# 2013_fdp_banc_de_test.net
KiCad netlist of a schematic drawn in Altium Designer
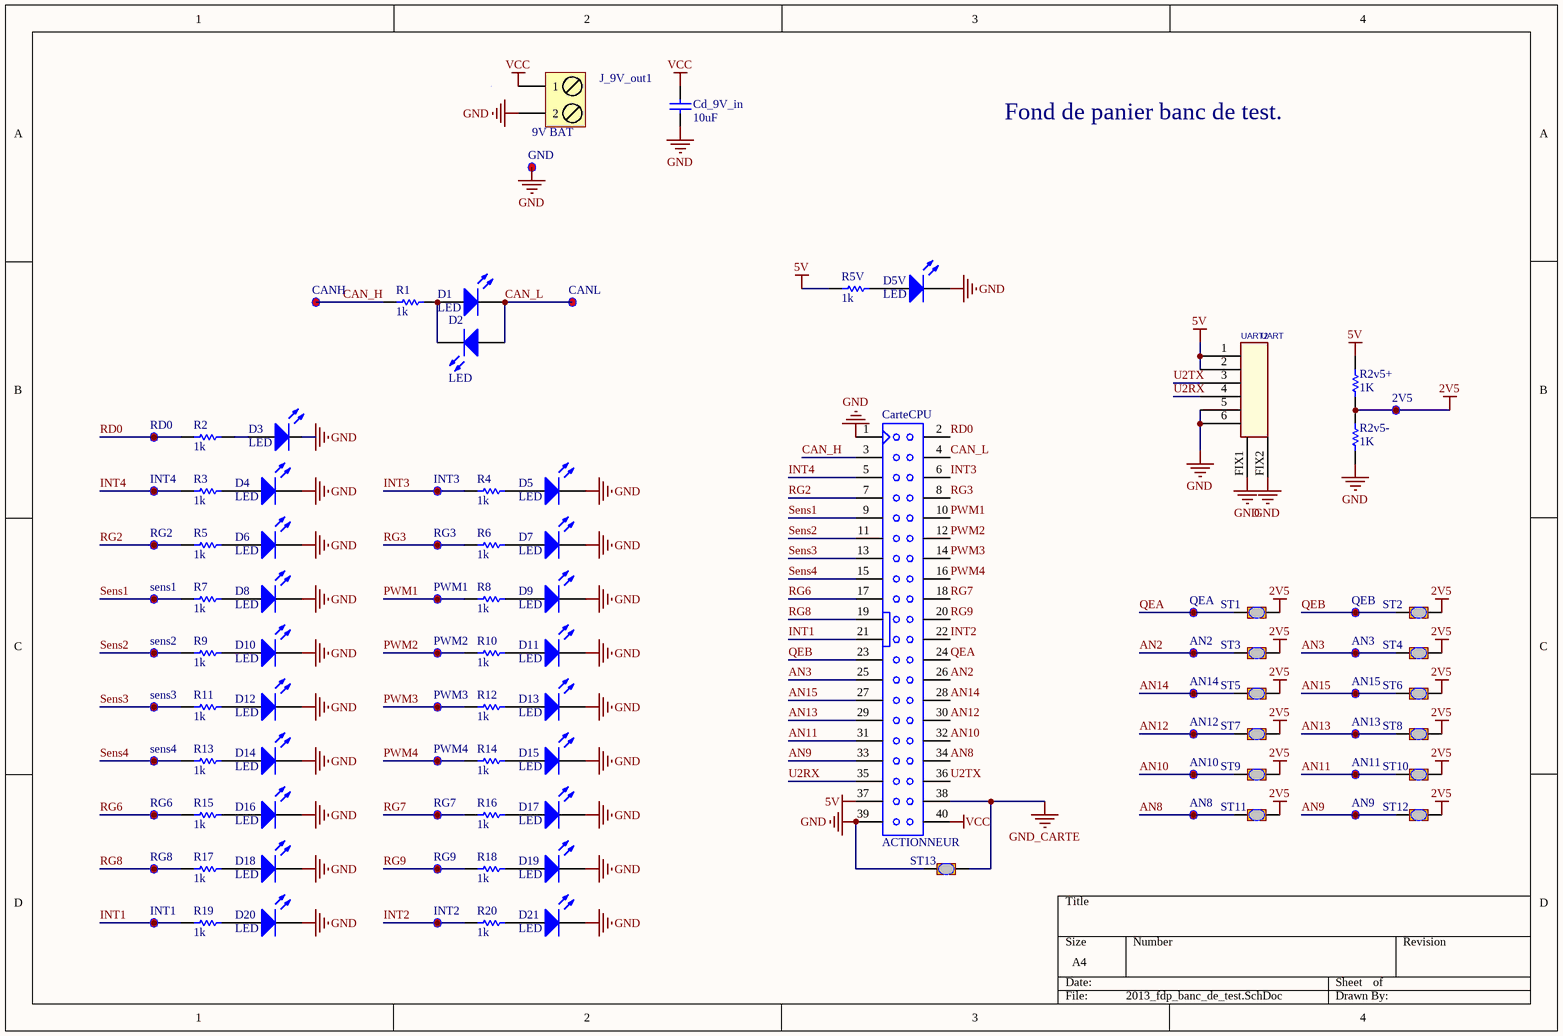
[diagram p0: 2013_fdp_banc_de_test.SchDoc]

(export (version "E")
  (design (tool "Eeschema 10.0.6"))
  (components
    (comp (ref "2V5")
      (value "Name")
      (footprint "Point Test_D0.9_P0.5mm")
      (description "Point test")
      (fields (field (name "PUBLISHER") "Damien GUITTON"))
      (libsource (lib "DG_Connecteur") (part "Point Test_2"))
    )
    (comp (ref "AN2")
      (value "Name")
      (footprint "Point Test_D0.9_P0.5mm")
      (description "Point test")
      (fields (field (name "PUBLISHER") "Damien GUITTON"))
      (libsource (lib "DG_Connecteur") (part "Point Test_2"))
    )
    (comp (ref "AN3")
      (value "Name")
      (footprint "Point Test_D0.9_P0.5mm")
      (description "Point test")
      (fields (field (name "PUBLISHER") "Damien GUITTON"))
      (libsource (lib "DG_Connecteur") (part "Point Test_2"))
    )
    (comp (ref "AN8")
      (value "Name")
      (footprint "Point Test_D0.9_P0.5mm")
      (description "Point test")
      (fields (field (name "PUBLISHER") "Damien GUITTON"))
      (libsource (lib "DG_Connecteur") (part "Point Test_2"))
    )
    (comp (ref "AN9")
      (value "Name")
      (footprint "Point Test_D0.9_P0.5mm")
      (description "Point test")
      (fields (field (name "PUBLISHER") "Damien GUITTON"))
      (libsource (lib "DG_Connecteur") (part "Point Test_2"))
    )
    (comp (ref "AN10")
      (value "Name")
      (footprint "Point Test_D0.9_P0.5mm")
      (description "Point test")
      (fields (field (name "PUBLISHER") "Damien GUITTON"))
      (libsource (lib "DG_Connecteur") (part "Point Test_2"))
    )
    (comp (ref "AN11")
      (value "Name")
      (footprint "Point Test_D0.9_P0.5mm")
      (description "Point test")
      (fields (field (name "PUBLISHER") "Damien GUITTON"))
      (libsource (lib "DG_Connecteur") (part "Point Test_2"))
    )
    (comp (ref "AN12")
      (value "Name")
      (footprint "Point Test_D0.9_P0.5mm")
      (description "Point test")
      (fields (field (name "PUBLISHER") "Damien GUITTON"))
      (libsource (lib "DG_Connecteur") (part "Point Test_2"))
    )
    (comp (ref "AN13")
      (value "Name")
      (footprint "Point Test_D0.9_P0.5mm")
      (description "Point test")
      (fields (field (name "PUBLISHER") "Damien GUITTON"))
      (libsource (lib "DG_Connecteur") (part "Point Test_2"))
    )
    (comp (ref "AN14")
      (value "Name")
      (footprint "Point Test_D0.9_P0.5mm")
      (description "Point test")
      (fields (field (name "PUBLISHER") "Damien GUITTON"))
      (libsource (lib "DG_Connecteur") (part "Point Test_2"))
    )
    (comp (ref "AN15")
      (value "Name")
      (footprint "Point Test_D0.9_P0.5mm")
      (description "Point test")
      (fields (field (name "PUBLISHER") "Damien GUITTON"))
      (libsource (lib "DG_Connecteur") (part "Point Test_2"))
    )
    (comp (ref "CANH")
      (value "Name")
      (footprint "Point Test_D0.9_P0.5mm")
      (description "Point test")
      (fields (field (name "PUBLISHER") "Damien GUITTON"))
      (libsource (lib "DG_Connecteur") (part "Point Test_2"))
    )
    (comp (ref "CANL")
      (value "Name")
      (footprint "Point Test_D0.9_P0.5mm")
      (description "Point test")
      (fields (field (name "PUBLISHER") "Damien GUITTON"))
      (libsource (lib "DG_Connecteur") (part "Point Test_2"))
    )
    (comp (ref "CarteCPU")
      (value "ACTIONNEUR")
      (footprint "HE10/40_MAL_DROIT-FDP-ROBOT")
      (description "Connector; HE10; 40 Position; Male")
      (libsource (lib "miniprojet") (part "HE10/40"))
    )
    (comp (ref "Cd_9V_in")
      (value "10uF")
      (footprint "C0805_N")
      (description "Capacitor")
      (fields (field (name "PUBLISHER") "Altium Limited"))
      (libsource (lib "_ROBOT") (part "Condensateur"))
    )
    (comp (ref "D1")
      (value "LED")
      (footprint "LED_0805")
      (description "Typical LED")
      (fields (field (name "PUBLISHER") "Altium Limited"))
      (libsource (lib "_ROBOT") (part "LED"))
    )
    (comp (ref "D2")
      (value "LED")
      (footprint "LED_0805")
      (description "Typical LED")
      (fields (field (name "PUBLISHER") "Altium Limited"))
      (libsource (lib "_ROBOT") (part "LED"))
    )
    (comp (ref "D3")
      (value "LED")
      (footprint "LED_0805")
      (description "Typical LED")
      (fields (field (name "PUBLISHER") "Altium Limited"))
      (libsource (lib "_ROBOT") (part "LED"))
    )
    (comp (ref "D4")
      (value "LED")
      (footprint "LED_0805")
      (description "Typical LED")
      (fields (field (name "PUBLISHER") "Altium Limited"))
      (libsource (lib "_ROBOT") (part "LED"))
    )
    (comp (ref "D5")
      (value "LED")
      (footprint "LED_0805")
      (description "Typical LED")
      (fields (field (name "PUBLISHER") "Altium Limited"))
      (libsource (lib "_ROBOT") (part "LED"))
    )
    (comp (ref "D5V")
      (value "LED")
      (footprint "LED_0805")
      (description "Typical LED")
      (fields (field (name "PUBLISHER") "Altium Limited"))
      (libsource (lib "_ROBOT") (part "LED"))
    )
    (comp (ref "D6")
      (value "LED")
      (footprint "LED_0805")
      (description "Typical LED")
      (fields (field (name "PUBLISHER") "Altium Limited"))
      (libsource (lib "_ROBOT") (part "LED"))
    )
    (comp (ref "D7")
      (value "LED")
      (footprint "LED_0805")
      (description "Typical LED")
      (fields (field (name "PUBLISHER") "Altium Limited"))
      (libsource (lib "_ROBOT") (part "LED"))
    )
    (comp (ref "D8")
      (value "LED")
      (footprint "LED_0805")
      (description "Typical LED")
      (fields (field (name "PUBLISHER") "Altium Limited"))
      (libsource (lib "_ROBOT") (part "LED"))
    )
    (comp (ref "D9")
      (value "LED")
      (footprint "LED_0805")
      (description "Typical LED")
      (fields (field (name "PUBLISHER") "Altium Limited"))
      (libsource (lib "_ROBOT") (part "LED"))
    )
    (comp (ref "D10")
      (value "LED")
      (footprint "LED_0805")
      (description "Typical LED")
      (fields (field (name "PUBLISHER") "Altium Limited"))
      (libsource (lib "_ROBOT") (part "LED"))
    )
    (comp (ref "D11")
      (value "LED")
      (footprint "LED_0805")
      (description "Typical LED")
      (fields (field (name "PUBLISHER") "Altium Limited"))
      (libsource (lib "_ROBOT") (part "LED"))
    )
    (comp (ref "D12")
      (value "LED")
      (footprint "LED_0805")
      (description "Typical LED")
      (fields (field (name "PUBLISHER") "Altium Limited"))
      (libsource (lib "_ROBOT") (part "LED"))
    )
    (comp (ref "D13")
      (value "LED")
      (footprint "LED_0805")
      (description "Typical LED")
      (fields (field (name "PUBLISHER") "Altium Limited"))
      (libsource (lib "_ROBOT") (part "LED"))
    )
    (comp (ref "D14")
      (value "LED")
      (footprint "LED_0805")
      (description "Typical LED")
      (fields (field (name "PUBLISHER") "Altium Limited"))
      (libsource (lib "_ROBOT") (part "LED"))
    )
    (comp (ref "D15")
      (value "LED")
      (footprint "LED_0805")
      (description "Typical LED")
      (fields (field (name "PUBLISHER") "Altium Limited"))
      (libsource (lib "_ROBOT") (part "LED"))
    )
    (comp (ref "D16")
      (value "LED")
      (footprint "LED_0805")
      (description "Typical LED")
      (fields (field (name "PUBLISHER") "Altium Limited"))
      (libsource (lib "_ROBOT") (part "LED"))
    )
    (comp (ref "D17")
      (value "LED")
      (footprint "LED_0805")
      (description "Typical LED")
      (fields (field (name "PUBLISHER") "Altium Limited"))
      (libsource (lib "_ROBOT") (part "LED"))
    )
    (comp (ref "D18")
      (value "LED")
      (footprint "LED_0805")
      (description "Typical LED")
      (fields (field (name "PUBLISHER") "Altium Limited"))
      (libsource (lib "_ROBOT") (part "LED"))
    )
    (comp (ref "D19")
      (value "LED")
      (footprint "LED_0805")
      (description "Typical LED")
      (fields (field (name "PUBLISHER") "Altium Limited"))
      (libsource (lib "_ROBOT") (part "LED"))
    )
    (comp (ref "D20")
      (value "LED")
      (footprint "LED_0805")
      (description "Typical LED")
      (fields (field (name "PUBLISHER") "Altium Limited"))
      (libsource (lib "_ROBOT") (part "LED"))
    )
    (comp (ref "D21")
      (value "LED")
      (footprint "LED_0805")
      (description "Typical LED")
      (fields (field (name "PUBLISHER") "Altium Limited"))
      (libsource (lib "_ROBOT") (part "LED"))
    )
    (comp (ref "GND")
      (value "Name")
      (footprint "Point Test_D0.9_P0.5mm")
      (description "Point test")
      (fields (field (name "PUBLISHER") "Damien GUITTON"))
      (libsource (lib "DG_Connecteur") (part "Point Test_2"))
    )
    (comp (ref "INT1")
      (value "Name")
      (footprint "Point Test_D0.9_P0.5mm")
      (description "Point test")
      (fields (field (name "PUBLISHER") "Damien GUITTON"))
      (libsource (lib "DG_Connecteur") (part "Point Test_2"))
    )
    (comp (ref "INT2")
      (value "Name")
      (footprint "Point Test_D0.9_P0.5mm")
      (description "Point test")
      (fields (field (name "PUBLISHER") "Damien GUITTON"))
      (libsource (lib "DG_Connecteur") (part "Point Test_2"))
    )
    (comp (ref "INT3")
      (value "Name")
      (footprint "Point Test_D0.9_P0.5mm")
      (description "Point test")
      (fields (field (name "PUBLISHER") "Damien GUITTON"))
      (libsource (lib "DG_Connecteur") (part "Point Test_2"))
    )
    (comp (ref "INT4")
      (value "Name")
      (footprint "Point Test_D0.9_P0.5mm")
      (description "Point test")
      (fields (field (name "PUBLISHER") "Damien GUITTON"))
      (libsource (lib "DG_Connecteur") (part "Point Test_2"))
    )
    (comp (ref "J_9V_out1")
      (value "9V BAT")
      (footprint "BORNIER2")
      (description "Terminal blocks, 2 pins, pitch=5mm")
      (libsource (lib "miniprojet") (part "BORNIER2"))
    )
    (comp (ref "PWM1")
      (value "Name")
      (footprint "Point Test_D0.9_P0.5mm")
      (description "Point test")
      (fields (field (name "PUBLISHER") "Damien GUITTON"))
      (libsource (lib "DG_Connecteur") (part "Point Test_2"))
    )
    (comp (ref "PWM2")
      (value "Name")
      (footprint "Point Test_D0.9_P0.5mm")
      (description "Point test")
      (fields (field (name "PUBLISHER") "Damien GUITTON"))
      (libsource (lib "DG_Connecteur") (part "Point Test_2"))
    )
    (comp (ref "PWM3")
      (value "Name")
      (footprint "Point Test_D0.9_P0.5mm")
      (description "Point test")
      (fields (field (name "PUBLISHER") "Damien GUITTON"))
      (libsource (lib "DG_Connecteur") (part "Point Test_2"))
    )
    (comp (ref "PWM4")
      (value "Name")
      (footprint "Point Test_D0.9_P0.5mm")
      (description "Point test")
      (fields (field (name "PUBLISHER") "Damien GUITTON"))
      (libsource (lib "DG_Connecteur") (part "Point Test_2"))
    )
    (comp (ref "QEA")
      (value "Name")
      (footprint "Point Test_D0.9_P0.5mm")
      (description "Point test")
      (fields (field (name "PUBLISHER") "Damien GUITTON"))
      (libsource (lib "DG_Connecteur") (part "Point Test_2"))
    )
    (comp (ref "QEB")
      (value "Name")
      (footprint "Point Test_D0.9_P0.5mm")
      (description "Point test")
      (fields (field (name "PUBLISHER") "Damien GUITTON"))
      (libsource (lib "DG_Connecteur") (part "Point Test_2"))
    )
    (comp (ref "R1")
      (value "1k")
      (footprint "R1206_N")
      (description "Resistor")
      (fields (field (name "PUBLISHER") "Altium Limited"))
      (libsource (lib "_ROBOT") (part "Resistor"))
    )
    (comp (ref "R2")
      (value "1k")
      (footprint "R1206_N")
      (description "Resistor")
      (fields (field (name "PUBLISHER") "Altium Limited"))
      (libsource (lib "_ROBOT") (part "Resistor"))
    )
    (comp (ref "R2v5+")
      (value "1K")
      (footprint "R1206_N")
      (description "Resistor")
      (fields (field (name "PUBLISHER") "Altium Limited"))
      (libsource (lib "_ROBOT") (part "Resistor"))
    )
    (comp (ref "R2v5-")
      (value "1K")
      (footprint "R1206_N")
      (description "Resistor")
      (fields (field (name "PUBLISHER") "Altium Limited"))
      (libsource (lib "_ROBOT") (part "Resistor"))
    )
    (comp (ref "R3")
      (value "1k")
      (footprint "R1206_N")
      (description "Resistor")
      (fields (field (name "PUBLISHER") "Altium Limited"))
      (libsource (lib "_ROBOT") (part "Resistor"))
    )
    (comp (ref "R4")
      (value "1k")
      (footprint "R1206_N")
      (description "Resistor")
      (fields (field (name "PUBLISHER") "Altium Limited"))
      (libsource (lib "_ROBOT") (part "Resistor"))
    )
    (comp (ref "R5")
      (value "1k")
      (footprint "R1206_N")
      (description "Resistor")
      (fields (field (name "PUBLISHER") "Altium Limited"))
      (libsource (lib "_ROBOT") (part "Resistor"))
    )
    (comp (ref "R5V")
      (value "1k")
      (footprint "R1206_N")
      (description "Resistor")
      (fields (field (name "PUBLISHER") "Altium Limited"))
      (libsource (lib "_ROBOT") (part "Resistor"))
    )
    (comp (ref "R6")
      (value "1k")
      (footprint "R1206_N")
      (description "Resistor")
      (fields (field (name "PUBLISHER") "Altium Limited"))
      (libsource (lib "_ROBOT") (part "Resistor"))
    )
    (comp (ref "R7")
      (value "1k")
      (footprint "R1206_N")
      (description "Resistor")
      (fields (field (name "PUBLISHER") "Altium Limited"))
      (libsource (lib "_ROBOT") (part "Resistor"))
    )
    (comp (ref "R8")
      (value "1k")
      (footprint "R1206_N")
      (description "Resistor")
      (fields (field (name "PUBLISHER") "Altium Limited"))
      (libsource (lib "_ROBOT") (part "Resistor"))
    )
    (comp (ref "R9")
      (value "1k")
      (footprint "R1206_N")
      (description "Resistor")
      (fields (field (name "PUBLISHER") "Altium Limited"))
      (libsource (lib "_ROBOT") (part "Resistor"))
    )
    (comp (ref "R10")
      (value "1k")
      (footprint "R1206_N")
      (description "Resistor")
      (fields (field (name "PUBLISHER") "Altium Limited"))
      (libsource (lib "_ROBOT") (part "Resistor"))
    )
    (comp (ref "R11")
      (value "1k")
      (footprint "R1206_N")
      (description "Resistor")
      (fields (field (name "PUBLISHER") "Altium Limited"))
      (libsource (lib "_ROBOT") (part "Resistor"))
    )
    (comp (ref "R12")
      (value "1k")
      (footprint "R1206_N")
      (description "Resistor")
      (fields (field (name "PUBLISHER") "Altium Limited"))
      (libsource (lib "_ROBOT") (part "Resistor"))
    )
    (comp (ref "R13")
      (value "1k")
      (footprint "R1206_N")
      (description "Resistor")
      (fields (field (name "PUBLISHER") "Altium Limited"))
      (libsource (lib "_ROBOT") (part "Resistor"))
    )
    (comp (ref "R14")
      (value "1k")
      (footprint "R1206_N")
      (description "Resistor")
      (fields (field (name "PUBLISHER") "Altium Limited"))
      (libsource (lib "_ROBOT") (part "Resistor"))
    )
    (comp (ref "R15")
      (value "1k")
      (footprint "R1206_N")
      (description "Resistor")
      (fields (field (name "PUBLISHER") "Altium Limited"))
      (libsource (lib "_ROBOT") (part "Resistor"))
    )
    (comp (ref "R16")
      (value "1k")
      (footprint "R1206_N")
      (description "Resistor")
      (fields (field (name "PUBLISHER") "Altium Limited"))
      (libsource (lib "_ROBOT") (part "Resistor"))
    )
    (comp (ref "R17")
      (value "1k")
      (footprint "R1206_N")
      (description "Resistor")
      (fields (field (name "PUBLISHER") "Altium Limited"))
      (libsource (lib "_ROBOT") (part "Resistor"))
    )
    (comp (ref "R18")
      (value "1k")
      (footprint "R1206_N")
      (description "Resistor")
      (fields (field (name "PUBLISHER") "Altium Limited"))
      (libsource (lib "_ROBOT") (part "Resistor"))
    )
    (comp (ref "R19")
      (value "1k")
      (footprint "R1206_N")
      (description "Resistor")
      (fields (field (name "PUBLISHER") "Altium Limited"))
      (libsource (lib "_ROBOT") (part "Resistor"))
    )
    (comp (ref "R20")
      (value "1k")
      (footprint "R1206_N")
      (description "Resistor")
      (fields (field (name "PUBLISHER") "Altium Limited"))
      (libsource (lib "_ROBOT") (part "Resistor"))
    )
    (comp (ref "RD0")
      (value "Name")
      (footprint "Point Test_D0.9_P0.5mm")
      (description "Point test")
      (fields (field (name "PUBLISHER") "Damien GUITTON"))
      (libsource (lib "DG_Connecteur") (part "Point Test_2"))
    )
    (comp (ref "RG2")
      (value "Name")
      (footprint "Point Test_D0.9_P0.5mm")
      (description "Point test")
      (fields (field (name "PUBLISHER") "Damien GUITTON"))
      (libsource (lib "DG_Connecteur") (part "Point Test_2"))
    )
    (comp (ref "RG3")
      (value "Name")
      (footprint "Point Test_D0.9_P0.5mm")
      (description "Point test")
      (fields (field (name "PUBLISHER") "Damien GUITTON"))
      (libsource (lib "DG_Connecteur") (part "Point Test_2"))
    )
    (comp (ref "RG6")
      (value "Name")
      (footprint "Point Test_D0.9_P0.5mm")
      (description "Point test")
      (fields (field (name "PUBLISHER") "Damien GUITTON"))
      (libsource (lib "DG_Connecteur") (part "Point Test_2"))
    )
    (comp (ref "RG7")
      (value "Name")
      (footprint "Point Test_D0.9_P0.5mm")
      (description "Point test")
      (fields (field (name "PUBLISHER") "Damien GUITTON"))
      (libsource (lib "DG_Connecteur") (part "Point Test_2"))
    )
    (comp (ref "RG8")
      (value "Name")
      (footprint "Point Test_D0.9_P0.5mm")
      (description "Point test")
      (fields (field (name "PUBLISHER") "Damien GUITTON"))
      (libsource (lib "DG_Connecteur") (part "Point Test_2"))
    )
    (comp (ref "RG9")
      (value "Name")
      (footprint "Point Test_D0.9_P0.5mm")
      (description "Point test")
      (fields (field (name "PUBLISHER") "Damien GUITTON"))
      (libsource (lib "DG_Connecteur") (part "Point Test_2"))
    )
    (comp (ref "sens1")
      (value "Name")
      (footprint "Point Test_D0.9_P0.5mm")
      (description "Point test")
      (fields (field (name "PUBLISHER") "Damien GUITTON"))
      (libsource (lib "DG_Connecteur") (part "Point Test_2"))
    )
    (comp (ref "sens2")
      (value "Name")
      (footprint "Point Test_D0.9_P0.5mm")
      (description "Point test")
      (fields (field (name "PUBLISHER") "Damien GUITTON"))
      (libsource (lib "DG_Connecteur") (part "Point Test_2"))
    )
    (comp (ref "sens3")
      (value "Name")
      (footprint "Point Test_D0.9_P0.5mm")
      (description "Point test")
      (fields (field (name "PUBLISHER") "Damien GUITTON"))
      (libsource (lib "DG_Connecteur") (part "Point Test_2"))
    )
    (comp (ref "sens4")
      (value "Name")
      (footprint "Point Test_D0.9_P0.5mm")
      (description "Point test")
      (fields (field (name "PUBLISHER") "Damien GUITTON"))
      (libsource (lib "DG_Connecteur") (part "Point Test_2"))
    )
    (comp (ref "ST1")
      (value "Goutte Strap_2")
      (footprint "Goutte Strap_2 Pads_Clearance 0.254mm")
      (fields (field (name "PUBLISHER") "Damien Guitton"))
      (libsource (lib "DG_Connecteur") (part "Goutte Strap_2"))
    )
    (comp (ref "ST2")
      (value "Goutte Strap_2")
      (footprint "Goutte Strap_2 Pads_Clearance 0.254mm")
      (fields (field (name "PUBLISHER") "Damien Guitton"))
      (libsource (lib "DG_Connecteur") (part "Goutte Strap_2"))
    )
    (comp (ref "ST3")
      (value "Goutte Strap_2")
      (footprint "Goutte Strap_2 Pads_Clearance 0.254mm")
      (fields (field (name "PUBLISHER") "Damien Guitton"))
      (libsource (lib "DG_Connecteur") (part "Goutte Strap_2"))
    )
    (comp (ref "ST4")
      (value "Goutte Strap_2")
      (footprint "Goutte Strap_2 Pads_Clearance 0.254mm")
      (fields (field (name "PUBLISHER") "Damien Guitton"))
      (libsource (lib "DG_Connecteur") (part "Goutte Strap_2"))
    )
    (comp (ref "ST5")
      (value "Goutte Strap_2")
      (footprint "Goutte Strap_2 Pads_Clearance 0.254mm")
      (fields (field (name "PUBLISHER") "Damien Guitton"))
      (libsource (lib "DG_Connecteur") (part "Goutte Strap_2"))
    )
    (comp (ref "ST6")
      (value "Goutte Strap_2")
      (footprint "Goutte Strap_2 Pads_Clearance 0.254mm")
      (fields (field (name "PUBLISHER") "Damien Guitton"))
      (libsource (lib "DG_Connecteur") (part "Goutte Strap_2"))
    )
    (comp (ref "ST7")
      (value "Goutte Strap_2")
      (footprint "Goutte Strap_2 Pads_Clearance 0.254mm")
      (fields (field (name "PUBLISHER") "Damien Guitton"))
      (libsource (lib "DG_Connecteur") (part "Goutte Strap_2"))
    )
    (comp (ref "ST8")
      (value "Goutte Strap_2")
      (footprint "Goutte Strap_2 Pads_Clearance 0.254mm")
      (fields (field (name "PUBLISHER") "Damien Guitton"))
      (libsource (lib "DG_Connecteur") (part "Goutte Strap_2"))
    )
    (comp (ref "ST9")
      (value "Goutte Strap_2")
      (footprint "Goutte Strap_2 Pads_Clearance 0.254mm")
      (fields (field (name "PUBLISHER") "Damien Guitton"))
      (libsource (lib "DG_Connecteur") (part "Goutte Strap_2"))
    )
    (comp (ref "ST10")
      (value "Goutte Strap_2")
      (footprint "Goutte Strap_2 Pads_Clearance 0.254mm")
      (fields (field (name "PUBLISHER") "Damien Guitton"))
      (libsource (lib "DG_Connecteur") (part "Goutte Strap_2"))
    )
    (comp (ref "ST11")
      (value "Goutte Strap_2")
      (footprint "Goutte Strap_2 Pads_Clearance 0.254mm")
      (fields (field (name "PUBLISHER") "Damien Guitton"))
      (libsource (lib "DG_Connecteur") (part "Goutte Strap_2"))
    )
    (comp (ref "ST12")
      (value "Goutte Strap_2")
      (footprint "Goutte Strap_2 Pads_Clearance 0.254mm")
      (fields (field (name "PUBLISHER") "Damien Guitton"))
      (libsource (lib "DG_Connecteur") (part "Goutte Strap_2"))
    )
    (comp (ref "ST13")
      (value "Goutte Strap_2")
      (footprint "Goutte Strap_2 Pads_Clearance 0.254mm")
      (fields (field (name "PUBLISHER") "Damien Guitton"))
      (libsource (lib "DG_Connecteur") (part "Goutte Strap_2"))
    )
    (comp (ref "UART2") (value "UART") (footprint "RJ11_6/6") (libsource (lib "*") (part "CONNECTEUR_RJ12")))
  )
  (nets
    (net (code "1") (name "/AN2") (class "Default")
      (node (ref "AN2") (pin "1") (pinfunction "1_1") (pintype "passive"))
      (node (ref "CarteCPU") (pin "26") (pinfunction "26_26") (pintype "passive"))
      (node (ref "ST3") (pin "1") (pinfunction "1_1") (pintype "passive"))
    )
    (net (code "2") (name "/AN3") (class "Default")
      (node (ref "AN3") (pin "1") (pinfunction "1_1") (pintype "passive"))
      (node (ref "CarteCPU") (pin "25") (pinfunction "25_25") (pintype "passive"))
      (node (ref "ST4") (pin "1") (pinfunction "1_1") (pintype "passive"))
    )
    (net (code "3") (name "/AN8") (class "Default")
      (node (ref "AN8") (pin "1") (pinfunction "1_1") (pintype "passive"))
      (node (ref "CarteCPU") (pin "34") (pinfunction "34_34") (pintype "passive"))
      (node (ref "ST11") (pin "1") (pinfunction "1_1") (pintype "passive"))
    )
    (net (code "4") (name "/AN9") (class "Default")
      (node (ref "AN9") (pin "1") (pinfunction "1_1") (pintype "passive"))
      (node (ref "CarteCPU") (pin "33") (pinfunction "33_33") (pintype "passive"))
      (node (ref "ST12") (pin "1") (pinfunction "1_1") (pintype "passive"))
    )
    (net (code "5") (name "/AN10") (class "Default")
      (node (ref "AN10") (pin "1") (pinfunction "1_1") (pintype "passive"))
      (node (ref "CarteCPU") (pin "32") (pinfunction "32_32") (pintype "passive"))
      (node (ref "ST9") (pin "1") (pinfunction "1_1") (pintype "passive"))
    )
    (net (code "6") (name "/AN11") (class "Default")
      (node (ref "AN11") (pin "1") (pinfunction "1_1") (pintype "passive"))
      (node (ref "CarteCPU") (pin "31") (pinfunction "31_31") (pintype "passive"))
      (node (ref "ST10") (pin "1") (pinfunction "1_1") (pintype "passive"))
    )
    (net (code "7") (name "/AN12") (class "Default")
      (node (ref "AN12") (pin "1") (pinfunction "1_1") (pintype "passive"))
      (node (ref "CarteCPU") (pin "30") (pinfunction "30_30") (pintype "passive"))
      (node (ref "ST7") (pin "1") (pinfunction "1_1") (pintype "passive"))
    )
    (net (code "8") (name "/AN13") (class "Default")
      (node (ref "AN13") (pin "1") (pinfunction "1_1") (pintype "passive"))
      (node (ref "CarteCPU") (pin "29") (pinfunction "29_29") (pintype "passive"))
      (node (ref "ST8") (pin "1") (pinfunction "1_1") (pintype "passive"))
    )
    (net (code "9") (name "/AN14") (class "Default")
      (node (ref "AN14") (pin "1") (pinfunction "1_1") (pintype "passive"))
      (node (ref "CarteCPU") (pin "28") (pinfunction "28_28") (pintype "passive"))
      (node (ref "ST5") (pin "1") (pinfunction "1_1") (pintype "passive"))
    )
    (net (code "10") (name "/AN15") (class "Default")
      (node (ref "AN15") (pin "1") (pinfunction "1_1") (pintype "passive"))
      (node (ref "CarteCPU") (pin "27") (pinfunction "27_27") (pintype "passive"))
      (node (ref "ST6") (pin "1") (pinfunction "1_1") (pintype "passive"))
    )
    (net (code "11") (name "/CAN_H") (class "Default")
      (node (ref "CANH") (pin "1") (pinfunction "1_1") (pintype "passive"))
      (node (ref "CarteCPU") (pin "3") (pinfunction "3_3") (pintype "passive"))
      (node (ref "R1") (pin "1") (pinfunction "1_1") (pintype "passive"))
    )
    (net (code "12") (name "/CAN_L") (class "Default")
      (node (ref "CANL") (pin "1") (pinfunction "1_1") (pintype "passive"))
      (node (ref "CarteCPU") (pin "4") (pinfunction "4_4") (pintype "passive"))
      (node (ref "D1") (pin "2") (pinfunction "K_2") (pintype "passive"))
      (node (ref "D2") (pin "1") (pinfunction "A_1") (pintype "passive"))
    )
    (net (code "13") (name "/INT1") (class "Default")
      (node (ref "CarteCPU") (pin "21") (pinfunction "21_21") (pintype "passive"))
      (node (ref "INT1") (pin "1") (pinfunction "1_1") (pintype "passive"))
      (node (ref "R19") (pin "1") (pinfunction "1_1") (pintype "passive"))
    )
    (net (code "14") (name "/INT2") (class "Default")
      (node (ref "CarteCPU") (pin "22") (pinfunction "22_22") (pintype "passive"))
      (node (ref "INT2") (pin "1") (pinfunction "1_1") (pintype "passive"))
      (node (ref "R20") (pin "1") (pinfunction "1_1") (pintype "passive"))
    )
    (net (code "15") (name "/INT3") (class "Default")
      (node (ref "CarteCPU") (pin "6") (pinfunction "6_6") (pintype "passive"))
      (node (ref "INT3") (pin "1") (pinfunction "1_1") (pintype "passive"))
      (node (ref "R4") (pin "1") (pinfunction "1_1") (pintype "passive"))
    )
    (net (code "16") (name "/INT4") (class "Default")
      (node (ref "CarteCPU") (pin "5") (pinfunction "5_5") (pintype "passive"))
      (node (ref "INT4") (pin "1") (pinfunction "1_1") (pintype "passive"))
      (node (ref "R3") (pin "1") (pinfunction "1_1") (pintype "passive"))
    )
    (net (code "17") (name "/PWM1") (class "Default")
      (node (ref "CarteCPU") (pin "10") (pinfunction "10_10") (pintype "passive"))
      (node (ref "PWM1") (pin "1") (pinfunction "1_1") (pintype "passive"))
      (node (ref "R8") (pin "1") (pinfunction "1_1") (pintype "passive"))
    )
    (net (code "18") (name "/PWM2") (class "Default")
      (node (ref "CarteCPU") (pin "12") (pinfunction "12_12") (pintype "passive"))
      (node (ref "PWM2") (pin "1") (pinfunction "1_1") (pintype "passive"))
      (node (ref "R10") (pin "1") (pinfunction "1_1") (pintype "passive"))
    )
    (net (code "19") (name "/PWM3") (class "Default")
      (node (ref "CarteCPU") (pin "14") (pinfunction "14_14") (pintype "passive"))
      (node (ref "PWM3") (pin "1") (pinfunction "1_1") (pintype "passive"))
      (node (ref "R12") (pin "1") (pinfunction "1_1") (pintype "passive"))
    )
    (net (code "20") (name "/PWM4") (class "Default")
      (node (ref "CarteCPU") (pin "16") (pinfunction "16_16") (pintype "passive"))
      (node (ref "PWM4") (pin "1") (pinfunction "1_1") (pintype "passive"))
      (node (ref "R14") (pin "1") (pinfunction "1_1") (pintype "passive"))
    )
    (net (code "21") (name "/QEA") (class "Default")
      (node (ref "CarteCPU") (pin "24") (pinfunction "24_24") (pintype "passive"))
      (node (ref "QEA") (pin "1") (pinfunction "1_1") (pintype "passive"))
      (node (ref "ST1") (pin "1") (pinfunction "1_1") (pintype "passive"))
    )
    (net (code "22") (name "/QEB") (class "Default")
      (node (ref "CarteCPU") (pin "23") (pinfunction "23_23") (pintype "passive"))
      (node (ref "QEB") (pin "1") (pinfunction "1_1") (pintype "passive"))
      (node (ref "ST2") (pin "1") (pinfunction "1_1") (pintype "passive"))
    )
    (net (code "23") (name "/RD0") (class "Default")
      (node (ref "CarteCPU") (pin "2") (pinfunction "2_2") (pintype "passive"))
      (node (ref "R2") (pin "1") (pinfunction "1_1") (pintype "passive"))
      (node (ref "RD0") (pin "1") (pinfunction "1_1") (pintype "passive"))
    )
    (net (code "24") (name "/RG2") (class "Default")
      (node (ref "CarteCPU") (pin "7") (pinfunction "7_7") (pintype "passive"))
      (node (ref "R5") (pin "1") (pinfunction "1_1") (pintype "passive"))
      (node (ref "RG2") (pin "1") (pinfunction "1_1") (pintype "passive"))
    )
    (net (code "25") (name "/RG3") (class "Default")
      (node (ref "CarteCPU") (pin "8") (pinfunction "8_8") (pintype "passive"))
      (node (ref "R6") (pin "1") (pinfunction "1_1") (pintype "passive"))
      (node (ref "RG3") (pin "1") (pinfunction "1_1") (pintype "passive"))
    )
    (net (code "26") (name "/RG6") (class "Default")
      (node (ref "CarteCPU") (pin "17") (pinfunction "17_17") (pintype "passive"))
      (node (ref "R15") (pin "1") (pinfunction "1_1") (pintype "passive"))
      (node (ref "RG6") (pin "1") (pinfunction "1_1") (pintype "passive"))
    )
    (net (code "27") (name "/RG7") (class "Default")
      (node (ref "CarteCPU") (pin "18") (pinfunction "18_18") (pintype "passive"))
      (node (ref "R16") (pin "1") (pinfunction "1_1") (pintype "passive"))
      (node (ref "RG7") (pin "1") (pinfunction "1_1") (pintype "passive"))
    )
    (net (code "28") (name "/RG8") (class "Default")
      (node (ref "CarteCPU") (pin "19") (pinfunction "19_19") (pintype "passive"))
      (node (ref "R17") (pin "1") (pinfunction "1_1") (pintype "passive"))
      (node (ref "RG8") (pin "1") (pinfunction "1_1") (pintype "passive"))
    )
    (net (code "29") (name "/RG9") (class "Default")
      (node (ref "CarteCPU") (pin "20") (pinfunction "20_20") (pintype "passive"))
      (node (ref "R18") (pin "1") (pinfunction "1_1") (pintype "passive"))
      (node (ref "RG9") (pin "1") (pinfunction "1_1") (pintype "passive"))
    )
    (net (code "30") (name "/Sens1") (class "Default")
      (node (ref "CarteCPU") (pin "9") (pinfunction "9_9") (pintype "passive"))
      (node (ref "R7") (pin "1") (pinfunction "1_1") (pintype "passive"))
      (node (ref "sens1") (pin "1") (pinfunction "1_1") (pintype "passive"))
    )
    (net (code "31") (name "/Sens2") (class "Default")
      (node (ref "CarteCPU") (pin "11") (pinfunction "11_11") (pintype "passive"))
      (node (ref "R9") (pin "1") (pinfunction "1_1") (pintype "passive"))
      (node (ref "sens2") (pin "1") (pinfunction "1_1") (pintype "passive"))
    )
    (net (code "32") (name "/Sens3") (class "Default")
      (node (ref "CarteCPU") (pin "13") (pinfunction "13_13") (pintype "passive"))
      (node (ref "R11") (pin "1") (pinfunction "1_1") (pintype "passive"))
      (node (ref "sens3") (pin "1") (pinfunction "1_1") (pintype "passive"))
    )
    (net (code "33") (name "/Sens4") (class "Default")
      (node (ref "CarteCPU") (pin "15") (pinfunction "15_15") (pintype "passive"))
      (node (ref "R13") (pin "1") (pinfunction "1_1") (pintype "passive"))
      (node (ref "sens4") (pin "1") (pinfunction "1_1") (pintype "passive"))
    )
    (net (code "34") (name "/U2RX") (class "Default")
      (node (ref "CarteCPU") (pin "35") (pinfunction "35_35") (pintype "passive"))
      (node (ref "UART2") (pin "4") (pinfunction "4_4") (pintype "passive"))
    )
    (net (code "35") (name "/U2TX") (class "Default")
      (node (ref "CarteCPU") (pin "36") (pinfunction "36_36") (pintype "passive"))
      (node (ref "UART2") (pin "3") (pinfunction "3_3") (pintype "passive"))
    )
    (net (code "36") (name "2V5") (class "Default")
      (node (ref "2V5") (pin "1") (pinfunction "1_1") (pintype "passive"))
      (node (ref "R2v5+") (pin "1") (pinfunction "1_1") (pintype "passive"))
      (node (ref "R2v5-") (pin "2") (pinfunction "2_2") (pintype "passive"))
      (node (ref "ST1") (pin "2") (pinfunction "2_2") (pintype "passive"))
      (node (ref "ST10") (pin "2") (pinfunction "2_2") (pintype "passive"))
      (node (ref "ST11") (pin "2") (pinfunction "2_2") (pintype "passive"))
      (node (ref "ST12") (pin "2") (pinfunction "2_2") (pintype "passive"))
      (node (ref "ST2") (pin "2") (pinfunction "2_2") (pintype "passive"))
      (node (ref "ST3") (pin "2") (pinfunction "2_2") (pintype "passive"))
      (node (ref "ST4") (pin "2") (pinfunction "2_2") (pintype "passive"))
      (node (ref "ST5") (pin "2") (pinfunction "2_2") (pintype "passive"))
      (node (ref "ST6") (pin "2") (pinfunction "2_2") (pintype "passive"))
      (node (ref "ST7") (pin "2") (pinfunction "2_2") (pintype "passive"))
      (node (ref "ST8") (pin "2") (pinfunction "2_2") (pintype "passive"))
      (node (ref "ST9") (pin "2") (pinfunction "2_2") (pintype "passive"))
    )
    (net (code "37") (name "5V") (class "Default")
      (node (ref "CarteCPU") (pin "37") (pinfunction "37_37") (pintype "passive"))
      (node (ref "R2v5+") (pin "2") (pinfunction "2_2") (pintype "passive"))
      (node (ref "R5V") (pin "1") (pinfunction "1_1") (pintype "passive"))
      (node (ref "UART2") (pin "1") (pinfunction "1_1") (pintype "passive"))
      (node (ref "UART2") (pin "2") (pinfunction "2_2") (pintype "passive"))
    )
    (net (code "38") (name "GND") (class "Default")
      (node (ref "CarteCPU") (pin "1") (pinfunction "1_1") (pintype "passive"))
      (node (ref "CarteCPU") (pin "39") (pinfunction "39_39") (pintype "passive"))
      (node (ref "Cd_9V_in") (pin "1") (pinfunction "1_1") (pintype "passive"))
      (node (ref "D10") (pin "2") (pinfunction "K_2") (pintype "passive"))
      (node (ref "D11") (pin "2") (pinfunction "K_2") (pintype "passive"))
      (node (ref "D12") (pin "2") (pinfunction "K_2") (pintype "passive"))
      (node (ref "D13") (pin "2") (pinfunction "K_2") (pintype "passive"))
      (node (ref "D14") (pin "2") (pinfunction "K_2") (pintype "passive"))
      (node (ref "D15") (pin "2") (pinfunction "K_2") (pintype "passive"))
      (node (ref "D16") (pin "2") (pinfunction "K_2") (pintype "passive"))
      (node (ref "D17") (pin "2") (pinfunction "K_2") (pintype "passive"))
      (node (ref "D18") (pin "2") (pinfunction "K_2") (pintype "passive"))
      (node (ref "D19") (pin "2") (pinfunction "K_2") (pintype "passive"))
      (node (ref "D20") (pin "2") (pinfunction "K_2") (pintype "passive"))
      (node (ref "D21") (pin "2") (pinfunction "K_2") (pintype "passive"))
      (node (ref "D3") (pin "2") (pinfunction "K_2") (pintype "passive"))
      (node (ref "D4") (pin "2") (pinfunction "K_2") (pintype "passive"))
      (node (ref "D5") (pin "2") (pinfunction "K_2") (pintype "passive"))
      (node (ref "D5V") (pin "2") (pinfunction "K_2") (pintype "passive"))
      (node (ref "D6") (pin "2") (pinfunction "K_2") (pintype "passive"))
      (node (ref "D7") (pin "2") (pinfunction "K_2") (pintype "passive"))
      (node (ref "D8") (pin "2") (pinfunction "K_2") (pintype "passive"))
      (node (ref "D9") (pin "2") (pinfunction "K_2") (pintype "passive"))
      (node (ref "GND") (pin "1") (pinfunction "1_1") (pintype "passive"))
      (node (ref "J_9V_out1") (pin "2") (pinfunction "2_2") (pintype "passive"))
      (node (ref "R2v5-") (pin "1") (pinfunction "1_1") (pintype "passive"))
      (node (ref "ST13") (pin "1") (pinfunction "1_1") (pintype "passive"))
      (node (ref "UART2") (pin "5") (pinfunction "5_5") (pintype "passive"))
      (node (ref "UART2") (pin "6") (pinfunction "6_6") (pintype "passive"))
      (node (ref "UART2") (pin "FIX1") (pinfunction "FIX1_FIX1") (pintype "passive"))
      (node (ref "UART2") (pin "FIX2") (pinfunction "FIX2_FIX2") (pintype "passive"))
    )
    (net (code "39") (name "GND_CARTE") (class "Default")
      (node (ref "CarteCPU") (pin "38") (pinfunction "38_38") (pintype "passive"))
      (node (ref "ST13") (pin "2") (pinfunction "2_2") (pintype "passive"))
    )
    (net (code "40") (name "Net-(D1-A)") (class "Default")
      (node (ref "D1") (pin "1") (pinfunction "A_1") (pintype "passive"))
      (node (ref "D2") (pin "2") (pinfunction "K_2") (pintype "passive"))
      (node (ref "R1") (pin "2") (pinfunction "2_2") (pintype "passive"))
    )
    (net (code "41") (name "Net-(D3-A)") (class "Default")
      (node (ref "D3") (pin "1") (pinfunction "A_1") (pintype "passive"))
      (node (ref "R2") (pin "2") (pinfunction "2_2") (pintype "passive"))
    )
    (net (code "42") (name "Net-(D4-A)") (class "Default")
      (node (ref "D4") (pin "1") (pinfunction "A_1") (pintype "passive"))
      (node (ref "R3") (pin "2") (pinfunction "2_2") (pintype "passive"))
    )
    (net (code "43") (name "Net-(D5-A)") (class "Default")
      (node (ref "D5") (pin "1") (pinfunction "A_1") (pintype "passive"))
      (node (ref "R4") (pin "2") (pinfunction "2_2") (pintype "passive"))
    )
    (net (code "44") (name "Net-(D5V-A)") (class "Default")
      (node (ref "D5V") (pin "1") (pinfunction "A_1") (pintype "passive"))
      (node (ref "R5V") (pin "2") (pinfunction "2_2") (pintype "passive"))
    )
    (net (code "45") (name "Net-(D6-A)") (class "Default")
      (node (ref "D6") (pin "1") (pinfunction "A_1") (pintype "passive"))
      (node (ref "R5") (pin "2") (pinfunction "2_2") (pintype "passive"))
    )
    (net (code "46") (name "Net-(D7-A)") (class "Default")
      (node (ref "D7") (pin "1") (pinfunction "A_1") (pintype "passive"))
      (node (ref "R6") (pin "2") (pinfunction "2_2") (pintype "passive"))
    )
    (net (code "47") (name "Net-(D8-A)") (class "Default")
      (node (ref "D8") (pin "1") (pinfunction "A_1") (pintype "passive"))
      (node (ref "R7") (pin "2") (pinfunction "2_2") (pintype "passive"))
    )
    (net (code "48") (name "Net-(D9-A)") (class "Default")
      (node (ref "D9") (pin "1") (pinfunction "A_1") (pintype "passive"))
      (node (ref "R8") (pin "2") (pinfunction "2_2") (pintype "passive"))
    )
    (net (code "49") (name "Net-(D10-A)") (class "Default")
      (node (ref "D10") (pin "1") (pinfunction "A_1") (pintype "passive"))
      (node (ref "R9") (pin "2") (pinfunction "2_2") (pintype "passive"))
    )
    (net (code "50") (name "Net-(D11-A)") (class "Default")
      (node (ref "D11") (pin "1") (pinfunction "A_1") (pintype "passive"))
      (node (ref "R10") (pin "2") (pinfunction "2_2") (pintype "passive"))
    )
    (net (code "51") (name "Net-(D12-A)") (class "Default")
      (node (ref "D12") (pin "1") (pinfunction "A_1") (pintype "passive"))
      (node (ref "R11") (pin "2") (pinfunction "2_2") (pintype "passive"))
    )
    (net (code "52") (name "Net-(D13-A)") (class "Default")
      (node (ref "D13") (pin "1") (pinfunction "A_1") (pintype "passive"))
      (node (ref "R12") (pin "2") (pinfunction "2_2") (pintype "passive"))
    )
    (net (code "53") (name "Net-(D14-A)") (class "Default")
      (node (ref "D14") (pin "1") (pinfunction "A_1") (pintype "passive"))
      (node (ref "R13") (pin "2") (pinfunction "2_2") (pintype "passive"))
    )
    (net (code "54") (name "Net-(D15-A)") (class "Default")
      (node (ref "D15") (pin "1") (pinfunction "A_1") (pintype "passive"))
      (node (ref "R14") (pin "2") (pinfunction "2_2") (pintype "passive"))
    )
    (net (code "55") (name "Net-(D16-A)") (class "Default")
      (node (ref "D16") (pin "1") (pinfunction "A_1") (pintype "passive"))
      (node (ref "R15") (pin "2") (pinfunction "2_2") (pintype "passive"))
    )
    (net (code "56") (name "Net-(D17-A)") (class "Default")
      (node (ref "D17") (pin "1") (pinfunction "A_1") (pintype "passive"))
      (node (ref "R16") (pin "2") (pinfunction "2_2") (pintype "passive"))
    )
    (net (code "57") (name "Net-(D18-A)") (class "Default")
      (node (ref "D18") (pin "1") (pinfunction "A_1") (pintype "passive"))
      (node (ref "R17") (pin "2") (pinfunction "2_2") (pintype "passive"))
    )
    (net (code "58") (name "Net-(D19-A)") (class "Default")
      (node (ref "D19") (pin "1") (pinfunction "A_1") (pintype "passive"))
      (node (ref "R18") (pin "2") (pinfunction "2_2") (pintype "passive"))
    )
    (net (code "59") (name "Net-(D20-A)") (class "Default")
      (node (ref "D20") (pin "1") (pinfunction "A_1") (pintype "passive"))
      (node (ref "R19") (pin "2") (pinfunction "2_2") (pintype "passive"))
    )
    (net (code "60") (name "Net-(D21-A)") (class "Default")
      (node (ref "D21") (pin "1") (pinfunction "A_1") (pintype "passive"))
      (node (ref "R20") (pin "2") (pinfunction "2_2") (pintype "passive"))
    )
    (net (code "61") (name "VCC") (class "Default")
      (node (ref "CarteCPU") (pin "40") (pinfunction "40_40") (pintype "passive"))
      (node (ref "Cd_9V_in") (pin "2") (pinfunction "2_2") (pintype "passive"))
      (node (ref "J_9V_out1") (pin "1") (pinfunction "1_1") (pintype "passive"))
    )
  )
)
